# SparkRemoteInterface.net
KiCad netlist of a schematic drawn in EAGLE
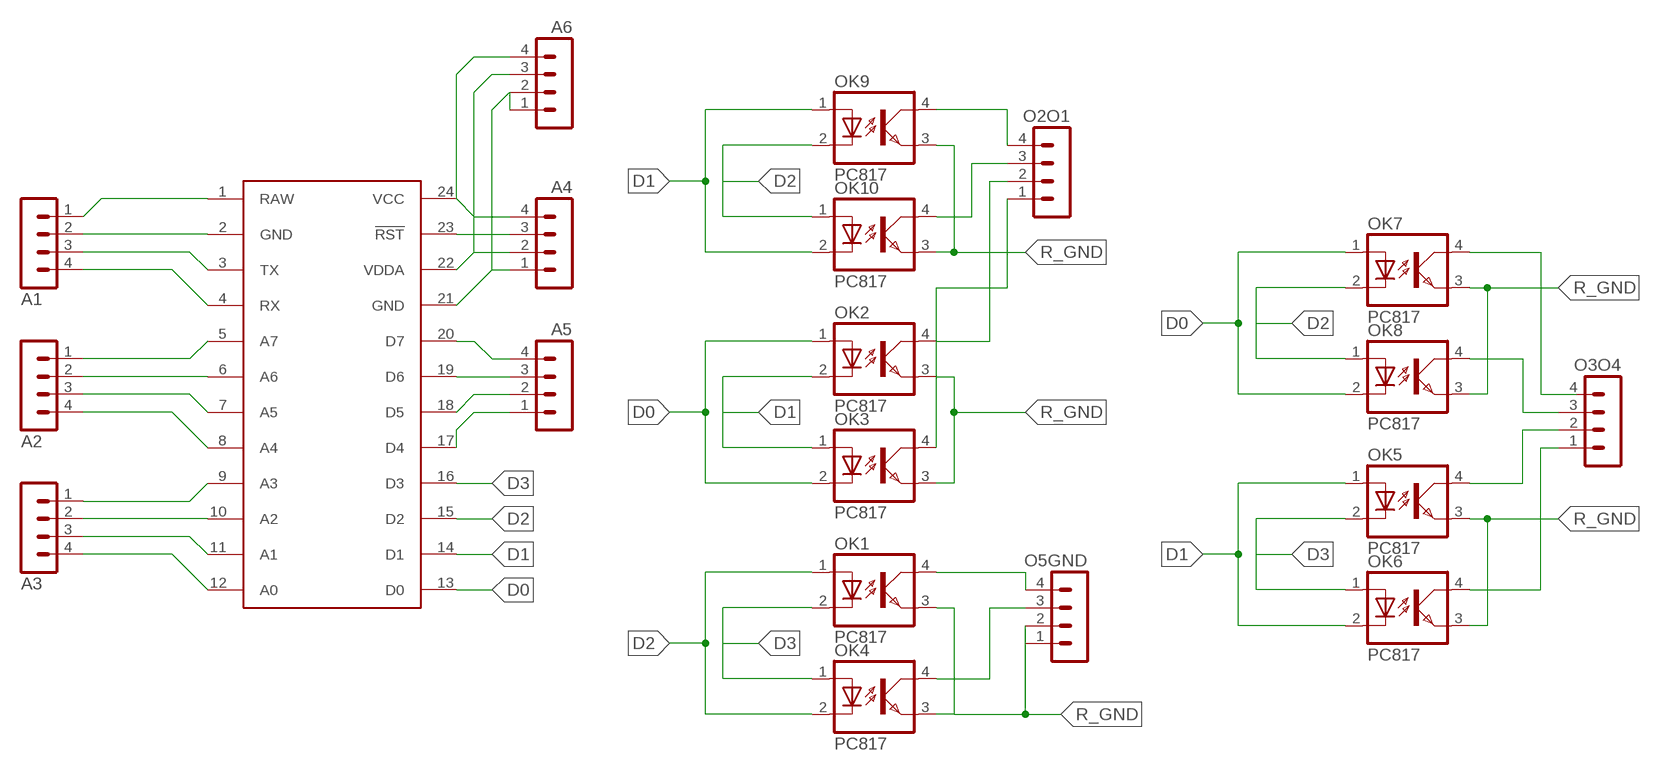
[diagram p0: schematic, sheet 1]

(export (version "E")
  (design (tool "Eeschema 10.0.6"))
  (components
    (comp (ref "A1")
      (value "MA04-1")
      (footprint "eagle-import:MA04-1")
      (libsource (lib "eagle-import") (part "MA04-1"))
    )
    (comp (ref "A2")
      (value "MA04-1")
      (footprint "eagle-import:MA04-1")
      (libsource (lib "eagle-import") (part "MA04-1"))
    )
    (comp (ref "A3")
      (value "MA04-1")
      (footprint "eagle-import:MA04-1")
      (libsource (lib "eagle-import") (part "MA04-1"))
    )
    (comp (ref "A4")
      (value "MA04-1")
      (footprint "eagle-import:MA04-1")
      (libsource (lib "eagle-import") (part "MA04-1"))
    )
    (comp (ref "A5")
      (value "MA04-1")
      (footprint "eagle-import:MA04-1")
      (libsource (lib "eagle-import") (part "MA04-1"))
    )
    (comp (ref "A6")
      (value "MA04-1")
      (footprint "eagle-import:MA04-1")
      (libsource (lib "eagle-import") (part "MA04-1"))
    )
    (comp (ref "O2O1")
      (value "MA04-1")
      (footprint "eagle-import:MA04-1")
      (libsource (lib "eagle-import") (part "MA04-1"))
    )
    (comp (ref "O3O4")
      (value "MA04-1")
      (footprint "eagle-import:MA04-1")
      (libsource (lib "eagle-import") (part "MA04-1"))
    )
    (comp (ref "O5GND")
      (value "MA04-1")
      (footprint "eagle-import:MA04-1")
      (libsource (lib "eagle-import") (part "MA04-1"))
    )
    (comp (ref "OK1")
      (value "PC817")
      (footprint "eagle-import:DIL04")
      (fields (field (name "MPN") "PC817X4J000F"))
      (libsource (lib "eagle-import") (part "PC817"))
    )
    (comp (ref "OK2")
      (value "PC817")
      (footprint "eagle-import:DIL04")
      (fields (field (name "MPN") "PC817X4J000F"))
      (libsource (lib "eagle-import") (part "PC817"))
    )
    (comp (ref "OK3")
      (value "PC817")
      (footprint "eagle-import:DIL04")
      (fields (field (name "MPN") "PC817X4J000F"))
      (libsource (lib "eagle-import") (part "PC817"))
    )
    (comp (ref "OK4")
      (value "PC817")
      (footprint "eagle-import:DIL04")
      (fields (field (name "MPN") "PC817X4J000F"))
      (libsource (lib "eagle-import") (part "PC817"))
    )
    (comp (ref "OK5")
      (value "PC817")
      (footprint "eagle-import:DIL04")
      (fields (field (name "MPN") "PC817X4J000F"))
      (libsource (lib "eagle-import") (part "PC817"))
    )
    (comp (ref "OK6")
      (value "PC817")
      (footprint "eagle-import:DIL04")
      (fields (field (name "MPN") "PC817X4J000F"))
      (libsource (lib "eagle-import") (part "PC817"))
    )
    (comp (ref "OK7")
      (value "PC817")
      (footprint "eagle-import:DIL04")
      (fields (field (name "MPN") "PC817X4J000F"))
      (libsource (lib "eagle-import") (part "PC817"))
    )
    (comp (ref "OK8")
      (value "PC817")
      (footprint "eagle-import:DIL04")
      (fields (field (name "MPN") "PC817X4J000F"))
      (libsource (lib "eagle-import") (part "PC817"))
    )
    (comp (ref "OK9")
      (value "PC817")
      (footprint "eagle-import:DIL04")
      (fields (field (name "MPN") "PC817X4J000F"))
      (libsource (lib "eagle-import") (part "PC817"))
    )
    (comp (ref "OK10")
      (value "PC817")
      (footprint "eagle-import:DIL04")
      (fields (field (name "MPN") "PC817X4J000F"))
      (libsource (lib "eagle-import") (part "PC817"))
    )
    (comp (ref "U$1")
      (value "SPARK_CORECORE")
      (footprint "eagle-import:SPARK_CORE")
      (libsource (lib "eagle-import") (part "SPARK_CORECORE"))
    )
  )
  (nets
    (net (code "1") (name "D0") (class "Default")
      (node (ref "OK2") (pin "1") (pinfunction "A_1") (pintype "passive"))
      (node (ref "OK3") (pin "2") (pinfunction "C_2") (pintype "passive"))
      (node (ref "OK7") (pin "1") (pinfunction "A_1") (pintype "passive"))
      (node (ref "OK8") (pin "2") (pinfunction "C_2") (pintype "passive"))
      (node (ref "U$1") (pin "13") (pinfunction "D0_13") (pintype "bidirectional"))
    )
    (net (code "2") (name "D1") (class "Default")
      (node (ref "OK10") (pin "2") (pinfunction "C_2") (pintype "passive"))
      (node (ref "OK2") (pin "2") (pinfunction "C_2") (pintype "passive"))
      (node (ref "OK3") (pin "1") (pinfunction "A_1") (pintype "passive"))
      (node (ref "OK5") (pin "1") (pinfunction "A_1") (pintype "passive"))
      (node (ref "OK6") (pin "2") (pinfunction "C_2") (pintype "passive"))
      (node (ref "OK9") (pin "1") (pinfunction "A_1") (pintype "passive"))
      (node (ref "U$1") (pin "14") (pinfunction "D1_14") (pintype "bidirectional"))
    )
    (net (code "3") (name "D2") (class "Default")
      (node (ref "OK1") (pin "1") (pinfunction "A_1") (pintype "passive"))
      (node (ref "OK10") (pin "1") (pinfunction "A_1") (pintype "passive"))
      (node (ref "OK4") (pin "2") (pinfunction "C_2") (pintype "passive"))
      (node (ref "OK7") (pin "2") (pinfunction "C_2") (pintype "passive"))
      (node (ref "OK8") (pin "1") (pinfunction "A_1") (pintype "passive"))
      (node (ref "OK9") (pin "2") (pinfunction "C_2") (pintype "passive"))
      (node (ref "U$1") (pin "15") (pinfunction "D2_15") (pintype "bidirectional"))
    )
    (net (code "4") (name "D3") (class "Default")
      (node (ref "OK1") (pin "2") (pinfunction "C_2") (pintype "passive"))
      (node (ref "OK4") (pin "1") (pinfunction "A_1") (pintype "passive"))
      (node (ref "OK5") (pin "2") (pinfunction "C_2") (pintype "passive"))
      (node (ref "OK6") (pin "1") (pinfunction "A_1") (pintype "passive"))
      (node (ref "U$1") (pin "16") (pinfunction "D3_16") (pintype "bidirectional"))
    )
    (net (code "5") (name "Net-(A1-Pad2)") (class "Default")
      (node (ref "A1") (pin "2") (pinfunction "2_2") (pintype "passive"))
      (node (ref "U$1") (pin "2") (pinfunction "GND_2") (pintype "power_in"))
    )
    (net (code "6") (name "Net-(A4-Pad1)") (class "Default")
      (node (ref "A4") (pin "1") (pinfunction "1_1") (pintype "passive"))
      (node (ref "A6") (pin "1") (pinfunction "1_1") (pintype "passive"))
      (node (ref "A6") (pin "2") (pinfunction "2_2") (pintype "passive"))
      (node (ref "U$1") (pin "21") (pinfunction "GND_21") (pintype "power_in"))
    )
    (net (code "7") (name "Net-(OK1-COL)") (class "Default")
      (node (ref "O5GND") (pin "4") (pinfunction "4_4") (pintype "passive"))
      (node (ref "OK1") (pin "4") (pinfunction "COL_4") (pintype "passive"))
    )
    (net (code "8") (name "Net-(OK2-COL)") (class "Default")
      (node (ref "O2O1") (pin "2") (pinfunction "2_2") (pintype "passive"))
      (node (ref "OK2") (pin "4") (pinfunction "COL_4") (pintype "passive"))
    )
    (net (code "9") (name "Net-(OK3-COL)") (class "Default")
      (node (ref "O2O1") (pin "1") (pinfunction "1_1") (pintype "passive"))
      (node (ref "OK3") (pin "4") (pinfunction "COL_4") (pintype "passive"))
    )
    (net (code "10") (name "Net-(OK4-COL)") (class "Default")
      (node (ref "O5GND") (pin "3") (pinfunction "3_3") (pintype "passive"))
      (node (ref "OK4") (pin "4") (pinfunction "COL_4") (pintype "passive"))
    )
    (net (code "11") (name "Net-(OK5-COL)") (class "Default")
      (node (ref "O3O4") (pin "2") (pinfunction "2_2") (pintype "passive"))
      (node (ref "OK5") (pin "4") (pinfunction "COL_4") (pintype "passive"))
    )
    (net (code "12") (name "Net-(OK6-COL)") (class "Default")
      (node (ref "O3O4") (pin "1") (pinfunction "1_1") (pintype "passive"))
      (node (ref "OK6") (pin "4") (pinfunction "COL_4") (pintype "passive"))
    )
    (net (code "13") (name "Net-(OK8-COL)") (class "Default")
      (node (ref "O3O4") (pin "3") (pinfunction "3_3") (pintype "passive"))
      (node (ref "OK8") (pin "4") (pinfunction "COL_4") (pintype "passive"))
    )
    (net (code "14") (name "Net-(OK9-COL)") (class "Default")
      (node (ref "O2O1") (pin "4") (pinfunction "4_4") (pintype "passive"))
      (node (ref "OK9") (pin "4") (pinfunction "COL_4") (pintype "passive"))
    )
    (net (code "15") (name "Net-(OK10-COL)") (class "Default")
      (node (ref "O2O1") (pin "3") (pinfunction "3_3") (pintype "passive"))
      (node (ref "OK10") (pin "4") (pinfunction "COL_4") (pintype "passive"))
    )
    (net (code "16") (name "Net-(U$1-A0)") (class "Default")
      (node (ref "A3") (pin "4") (pinfunction "4_4") (pintype "passive"))
      (node (ref "U$1") (pin "12") (pinfunction "A0_12") (pintype "bidirectional"))
    )
    (net (code "17") (name "Net-(U$1-A1)") (class "Default")
      (node (ref "A3") (pin "3") (pinfunction "3_3") (pintype "passive"))
      (node (ref "U$1") (pin "11") (pinfunction "A1_11") (pintype "bidirectional"))
    )
    (net (code "18") (name "Net-(U$1-A2)") (class "Default")
      (node (ref "A3") (pin "2") (pinfunction "2_2") (pintype "passive"))
      (node (ref "U$1") (pin "10") (pinfunction "A2_10") (pintype "bidirectional"))
    )
    (net (code "19") (name "Net-(U$1-A3)") (class "Default")
      (node (ref "A3") (pin "1") (pinfunction "1_1") (pintype "passive"))
      (node (ref "U$1") (pin "9") (pinfunction "A3_9") (pintype "bidirectional"))
    )
    (net (code "20") (name "Net-(U$1-A4)") (class "Default")
      (node (ref "A2") (pin "4") (pinfunction "4_4") (pintype "passive"))
      (node (ref "U$1") (pin "8") (pinfunction "A4_8") (pintype "bidirectional"))
    )
    (net (code "21") (name "Net-(U$1-A5)") (class "Default")
      (node (ref "A2") (pin "3") (pinfunction "3_3") (pintype "passive"))
      (node (ref "U$1") (pin "7") (pinfunction "A5_7") (pintype "bidirectional"))
    )
    (net (code "22") (name "Net-(U$1-A6)") (class "Default")
      (node (ref "A2") (pin "2") (pinfunction "2_2") (pintype "passive"))
      (node (ref "U$1") (pin "6") (pinfunction "A6_6") (pintype "bidirectional"))
    )
    (net (code "23") (name "Net-(U$1-A7)") (class "Default")
      (node (ref "A2") (pin "1") (pinfunction "1_1") (pintype "passive"))
      (node (ref "U$1") (pin "5") (pinfunction "A7_5") (pintype "bidirectional"))
    )
    (net (code "24") (name "Net-(U$1-D4)") (class "Default")
      (node (ref "A5") (pin "1") (pinfunction "1_1") (pintype "passive"))
      (node (ref "U$1") (pin "17") (pinfunction "D4_17") (pintype "bidirectional"))
    )
    (net (code "25") (name "Net-(U$1-D5)") (class "Default")
      (node (ref "A5") (pin "2") (pinfunction "2_2") (pintype "passive"))
      (node (ref "U$1") (pin "18") (pinfunction "D5_18") (pintype "bidirectional"))
    )
    (net (code "26") (name "Net-(U$1-D6)") (class "Default")
      (node (ref "A5") (pin "3") (pinfunction "3_3") (pintype "passive"))
      (node (ref "U$1") (pin "19") (pinfunction "D6_19") (pintype "bidirectional"))
    )
    (net (code "27") (name "Net-(U$1-D7)") (class "Default")
      (node (ref "A5") (pin "4") (pinfunction "4_4") (pintype "passive"))
      (node (ref "U$1") (pin "20") (pinfunction "D7_20") (pintype "bidirectional"))
    )
    (net (code "28") (name "Net-(U$1-RAW)") (class "Default")
      (node (ref "A1") (pin "1") (pinfunction "1_1") (pintype "passive"))
      (node (ref "U$1") (pin "1") (pinfunction "RAW_1") (pintype "power_in"))
    )
    (net (code "29") (name "Net-(U$1-RX)") (class "Default")
      (node (ref "A1") (pin "4") (pinfunction "4_4") (pintype "passive"))
      (node (ref "U$1") (pin "4") (pinfunction "RX_4") (pintype "bidirectional"))
    )
    (net (code "30") (name "Net-(U$1-TX)") (class "Default")
      (node (ref "A1") (pin "3") (pinfunction "3_3") (pintype "passive"))
      (node (ref "U$1") (pin "3") (pinfunction "TX_3") (pintype "bidirectional"))
    )
    (net (code "31") (name "Net-(U$1-VCC)") (class "Default")
      (node (ref "A4") (pin "4") (pinfunction "4_4") (pintype "passive"))
      (node (ref "A6") (pin "4") (pinfunction "4_4") (pintype "passive"))
      (node (ref "U$1") (pin "24") (pinfunction "VCC_24") (pintype "power_in"))
    )
    (net (code "32") (name "Net-(U$1-VDDA)") (class "Default")
      (node (ref "A4") (pin "2") (pinfunction "2_2") (pintype "passive"))
      (node (ref "A6") (pin "3") (pinfunction "3_3") (pintype "passive"))
      (node (ref "U$1") (pin "22") (pinfunction "VDDA_22") (pintype "power_in"))
    )
    (net (code "33") (name "Net-(U$1-~{RST})") (class "Default")
      (node (ref "A4") (pin "3") (pinfunction "3_3") (pintype "passive"))
      (node (ref "U$1") (pin "23") (pinfunction "~{RST}_23") (pintype "bidirectional"))
    )
    (net (code "34") (name "R_GND") (class "Default")
      (node (ref "O5GND") (pin "1") (pinfunction "1_1") (pintype "passive"))
      (node (ref "O5GND") (pin "2") (pinfunction "2_2") (pintype "passive"))
      (node (ref "OK1") (pin "3") (pinfunction "EMIT_3") (pintype "passive"))
      (node (ref "OK10") (pin "3") (pinfunction "EMIT_3") (pintype "passive"))
      (node (ref "OK2") (pin "3") (pinfunction "EMIT_3") (pintype "passive"))
      (node (ref "OK3") (pin "3") (pinfunction "EMIT_3") (pintype "passive"))
      (node (ref "OK4") (pin "3") (pinfunction "EMIT_3") (pintype "passive"))
      (node (ref "OK5") (pin "3") (pinfunction "EMIT_3") (pintype "passive"))
      (node (ref "OK6") (pin "3") (pinfunction "EMIT_3") (pintype "passive"))
      (node (ref "OK7") (pin "3") (pinfunction "EMIT_3") (pintype "passive"))
      (node (ref "OK8") (pin "3") (pinfunction "EMIT_3") (pintype "passive"))
      (node (ref "OK9") (pin "3") (pinfunction "EMIT_3") (pintype "passive"))
    )
    (net (code "35") (name "unconnected-(O3O4-Pad4)") (class "Default")
      (node (ref "O3O4") (pin "4") (pinfunction "4_4") (pintype "passive"))
    )
    (net (code "36") (name "unconnected-(OK7-COL-Pad4)") (class "Default")
      (node (ref "OK7") (pin "4") (pinfunction "COL_4") (pintype "passive"))
    )
  )
)
